# HSS.net
KiCad netlist of a schematic drawn in Altium Designer
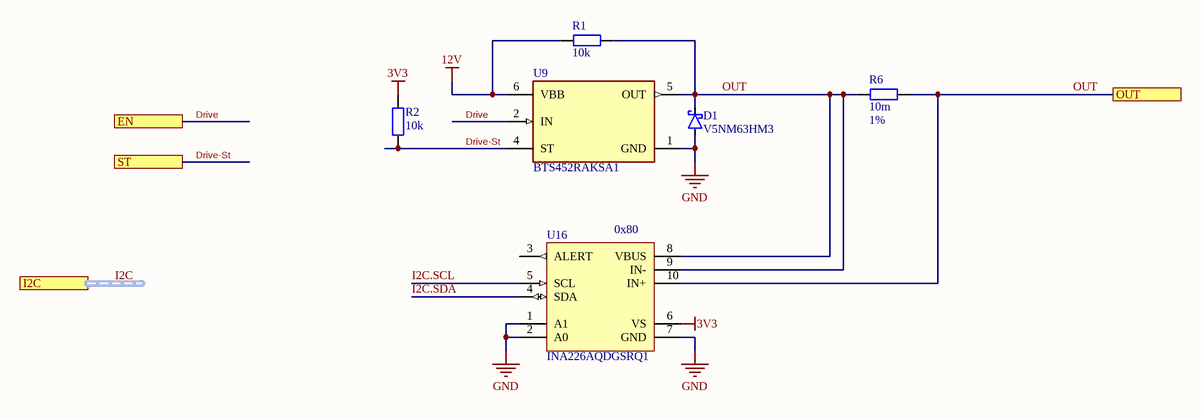
[diagram p0: HSS.SchDoc]

(export (version "E")
  (design (tool "Eeschema 10.0.6"))
  (components
    (comp (ref "D1")
      (value "V5NM63HM3")
      (footprint "DFN3820A")
      (description "Vishay - 5A, 60V Schottky diode, DFN3820A, DO-220AA compatible")
      (libsource (lib "AFR365") (part "SCHOTTKY_DIODE_SINGLE"))
    )
    (comp (ref "R1")
      (value "10k")
      (footprint "SMD_0603_RES")
      (description "RES SMD 10K OHM 1% 1/10W 0603 ±100ppm/°C")
      (fields (field (name "TOLERANCE") "1%") (field (name "POWER") "100mW"))
      (libsource (lib "AFR365") (part "resistor"))
    )
    (comp (ref "R2")
      (value "10k")
      (footprint "SMD_0603_RES")
      (description "RES SMD 10K OHM 1% 1/10W 0603 ±100ppm/°C")
      (fields (field (name "TOLERANCE") "1%") (field (name "POWER") "100mW"))
      (libsource (lib "AFR365") (part "resistor"))
    )
    (comp (ref "R6")
      (value "10m")
      (footprint "SMD_1206_RES")
      (description "RES SMD 0.01 OHM 1% 1 1206 ±200ppm/°C")
      (fields
        (field (name "TOLERANCE") "1%")
        (field (name "POWER") "1W")
        (field (name "Comment") "ERJ-8BWFR010V")
      )
      (libsource (lib "AFR365") (part "resistor"))
    )
    (comp (ref "U9")
      (value "BTS452RAKSA1")
      (footprint "FP-PG-TO252-5-MFG")
      (description "BTS452RAKSA1 Power Load Sw, High Side, -40 To 150Degc Rohs Compliant: Yes")
      (libsource (lib "Altium Content Vault") (part "67d4282830698c9d010d655e197f1c3"))
    )
    (comp (ref "U16")
      (value "INA226AQDGSRQ1")
      (footprint "TI-DGS0010A-VSSOP-10")
      (description "SP Amp Current Shunt and Power Monitor Dual 5.5V 10-Pin VSSOP T/R")
      (libsource (lib "AFR365") (part "INA228"))
    )
  )
  (nets
    (net (code "2") (name "/Drive") (class "Default")
      (node (ref "U9") (pin "2") (pinfunction "IN_2") (pintype "input"))
    )
    (net (code "3") (name "/Drive-St") (class "Default")
      (node (ref "R2") (pin "1") (pinfunction "1_1") (pintype "passive"))
      (node (ref "U9") (pin "4") (pinfunction "ST_4") (pintype "open_collector"))
    )
    (net (code "4") (name "/I2C.SCL") (class "Default")
      (node (ref "U16") (pin "5") (pinfunction "SCL_5") (pintype "input"))
    )
    (net (code "5") (name "/I2C.SDA") (class "Default")
      (node (ref "U16") (pin "4") (pinfunction "SDA_4") (pintype "bidirectional"))
    )
    (net (code "6") (name "/OUT") (class "Default")
      (node (ref "D1") (pin "1") (pinfunction "C_1") (pintype "passive"))
      (node (ref "R1") (pin "2") (pinfunction "2_2") (pintype "passive"))
      (node (ref "R6") (pin "1") (pinfunction "1_1") (pintype "passive"))
      (node (ref "R6") (pin "2") (pinfunction "2_2") (pintype "passive"))
      (node (ref "U16") (pin "10") (pinfunction "IN+_10") (pintype "power_in"))
      (node (ref "U16") (pin "8") (pinfunction "VBUS_8") (pintype "power_in"))
      (node (ref "U16") (pin "9") (pinfunction "IN-_9") (pintype "power_in"))
      (node (ref "U9") (pin "5") (pinfunction "OUT_5") (pintype "output"))
    )
    (net (code "8") (name "3V3") (class "Default")
      (node (ref "R2") (pin "2") (pinfunction "2_2") (pintype "passive"))
      (node (ref "U16") (pin "6") (pinfunction "VS_6") (pintype "power_in"))
    )
    (net (code "9") (name "12V") (class "Default")
      (node (ref "R1") (pin "1") (pinfunction "1_1") (pintype "passive"))
      (node (ref "U9") (pin "6") (pinfunction "VBB_6") (pintype "power_in"))
    )
    (net (code "10") (name "GND") (class "Default")
      (node (ref "D1") (pin "2") (pinfunction "A_2") (pintype "passive"))
      (node (ref "U16") (pin "1") (pinfunction "A1_1") (pintype "passive"))
      (node (ref "U16") (pin "2") (pinfunction "A0_2") (pintype "passive"))
      (node (ref "U16") (pin "7") (pinfunction "GND_7") (pintype "power_in"))
      (node (ref "U9") (pin "1") (pinfunction "GND_1") (pintype "power_in"))
    )
    (net (code "11") (name "unconnected-(U16-ALERT-Pad3)") (class "Default")
      (node (ref "U16") (pin "3") (pinfunction "ALERT_3") (pintype "output"))
    )
  )
)
